# QDC.net
KiCad netlist of a schematic drawn in Altium Designer
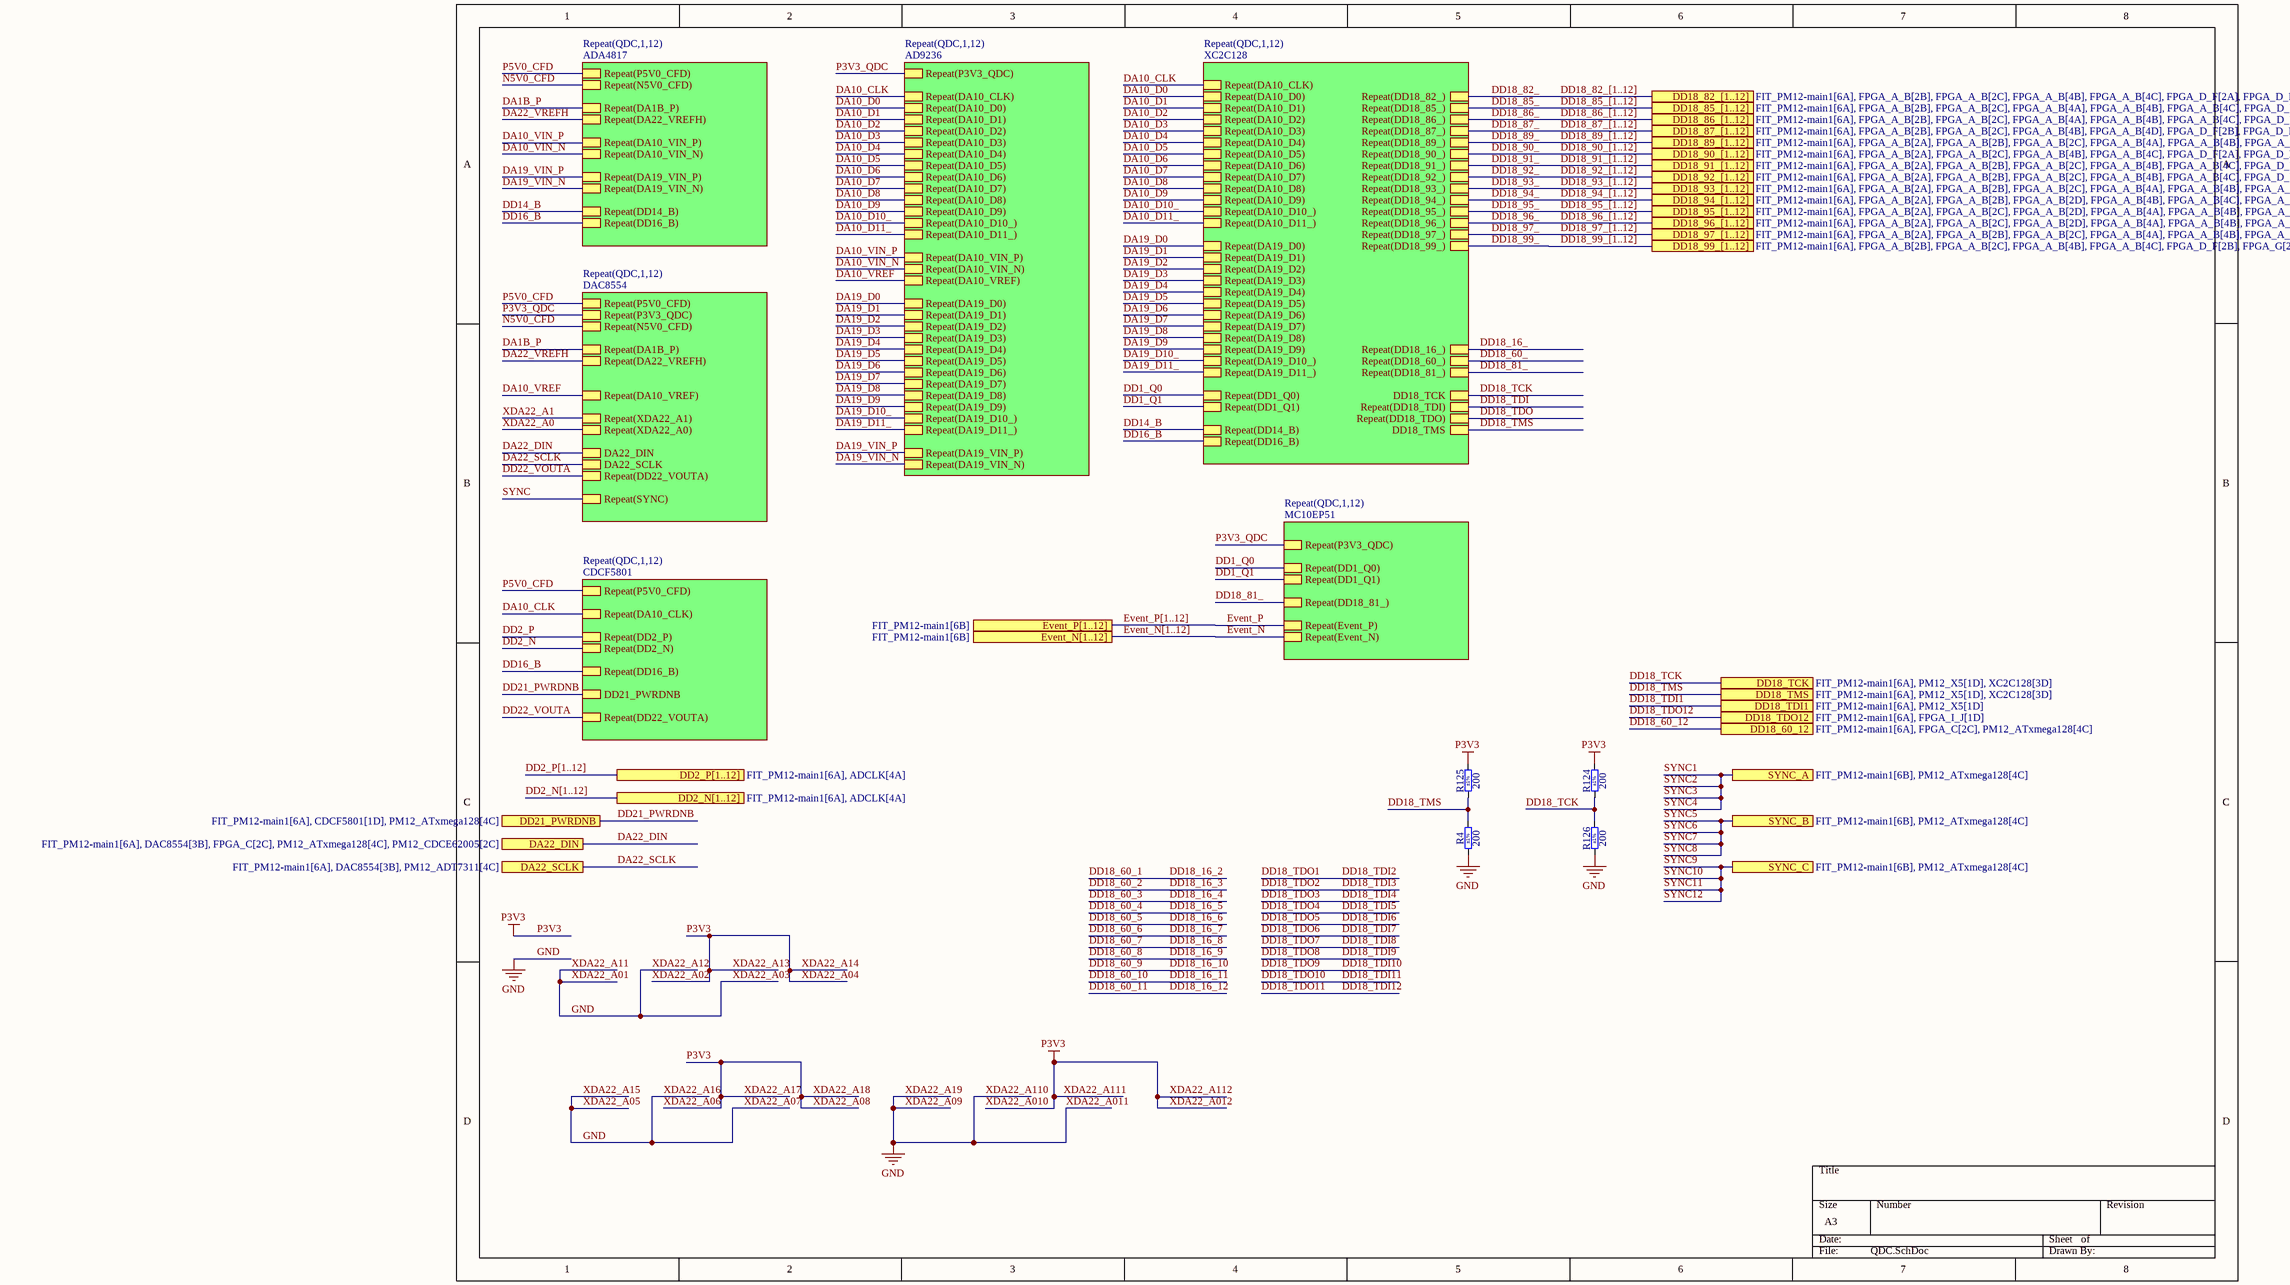
[diagram p0: QDC.SchDoc]

(export (version "E")
  (design (tool "Eeschema 10.0.6"))
  (components
    (comp (ref "R4")
      (value "200")
      (footprint "RESC2012X60N")
      (description "Resistor - 1%")
      (fields
        (field (name "TOLERANCE") "±1%")
        (field (name "PART NUMBER") "R0805_200R_1%_0.125W_100PPM")
        (field (name "POWER") "0.125W")
        (field (name "AUTHOR") "CERN DEM JLC")
      )
      (libsource (lib "Resistors") (part "Resistor - 1%"))
    )
    (comp (ref "R124")
      (value "200")
      (footprint "RESC2012X60N")
      (description "Resistor - 1%")
      (fields
        (field (name "TOLERANCE") "±1%")
        (field (name "PART NUMBER") "R0805_200R_1%_0.125W_100PPM")
        (field (name "POWER") "0.125W")
        (field (name "AUTHOR") "CERN DEM JLC")
      )
      (libsource (lib "Resistors") (part "Resistor - 1%"))
    )
    (comp (ref "R125")
      (value "200")
      (footprint "RESC2012X60N")
      (description "Resistor - 1%")
      (fields
        (field (name "TOLERANCE") "±1%")
        (field (name "PART NUMBER") "R0805_200R_1%_0.125W_100PPM")
        (field (name "POWER") "0.125W")
        (field (name "AUTHOR") "CERN DEM JLC")
      )
      (libsource (lib "Resistors") (part "Resistor - 1%"))
    )
    (comp (ref "R126")
      (value "200")
      (footprint "RESC2012X60N")
      (description "Resistor - 1%")
      (fields
        (field (name "TOLERANCE") "±1%")
        (field (name "PART NUMBER") "R0805_200R_1%_0.125W_100PPM")
        (field (name "POWER") "0.125W")
        (field (name "AUTHOR") "CERN DEM JLC")
      )
      (libsource (lib "Resistors") (part "Resistor - 1%"))
    )
  )
  (nets
    (net (code "302") (name "/DD18_TCK") (class "Default")
      (node (ref "R124") (pin "1") (pinfunction "1_1") (pintype "passive"))
      (node (ref "R126") (pin "2") (pinfunction "2_2") (pintype "passive"))
    )
    (net (code "318") (name "/DD18_TMS") (class "Default")
      (node (ref "R125") (pin "1") (pinfunction "1_1") (pintype "passive"))
      (node (ref "R4") (pin "2") (pinfunction "2_2") (pintype "passive"))
    )
    (net (code "334") (name "GND") (class "Default")
      (node (ref "R126") (pin "1") (pinfunction "1_1") (pintype "passive"))
      (node (ref "R4") (pin "1") (pinfunction "1_1") (pintype "passive"))
    )
    (net (code "335") (name "P3V3") (class "Default")
      (node (ref "R124") (pin "2") (pinfunction "2_2") (pintype "passive"))
      (node (ref "R125") (pin "2") (pinfunction "2_2") (pintype "passive"))
    )
  )
)
